# motor_shield__SD_v2_0.net
KiCad netlist of a schematic drawn in EAGLE
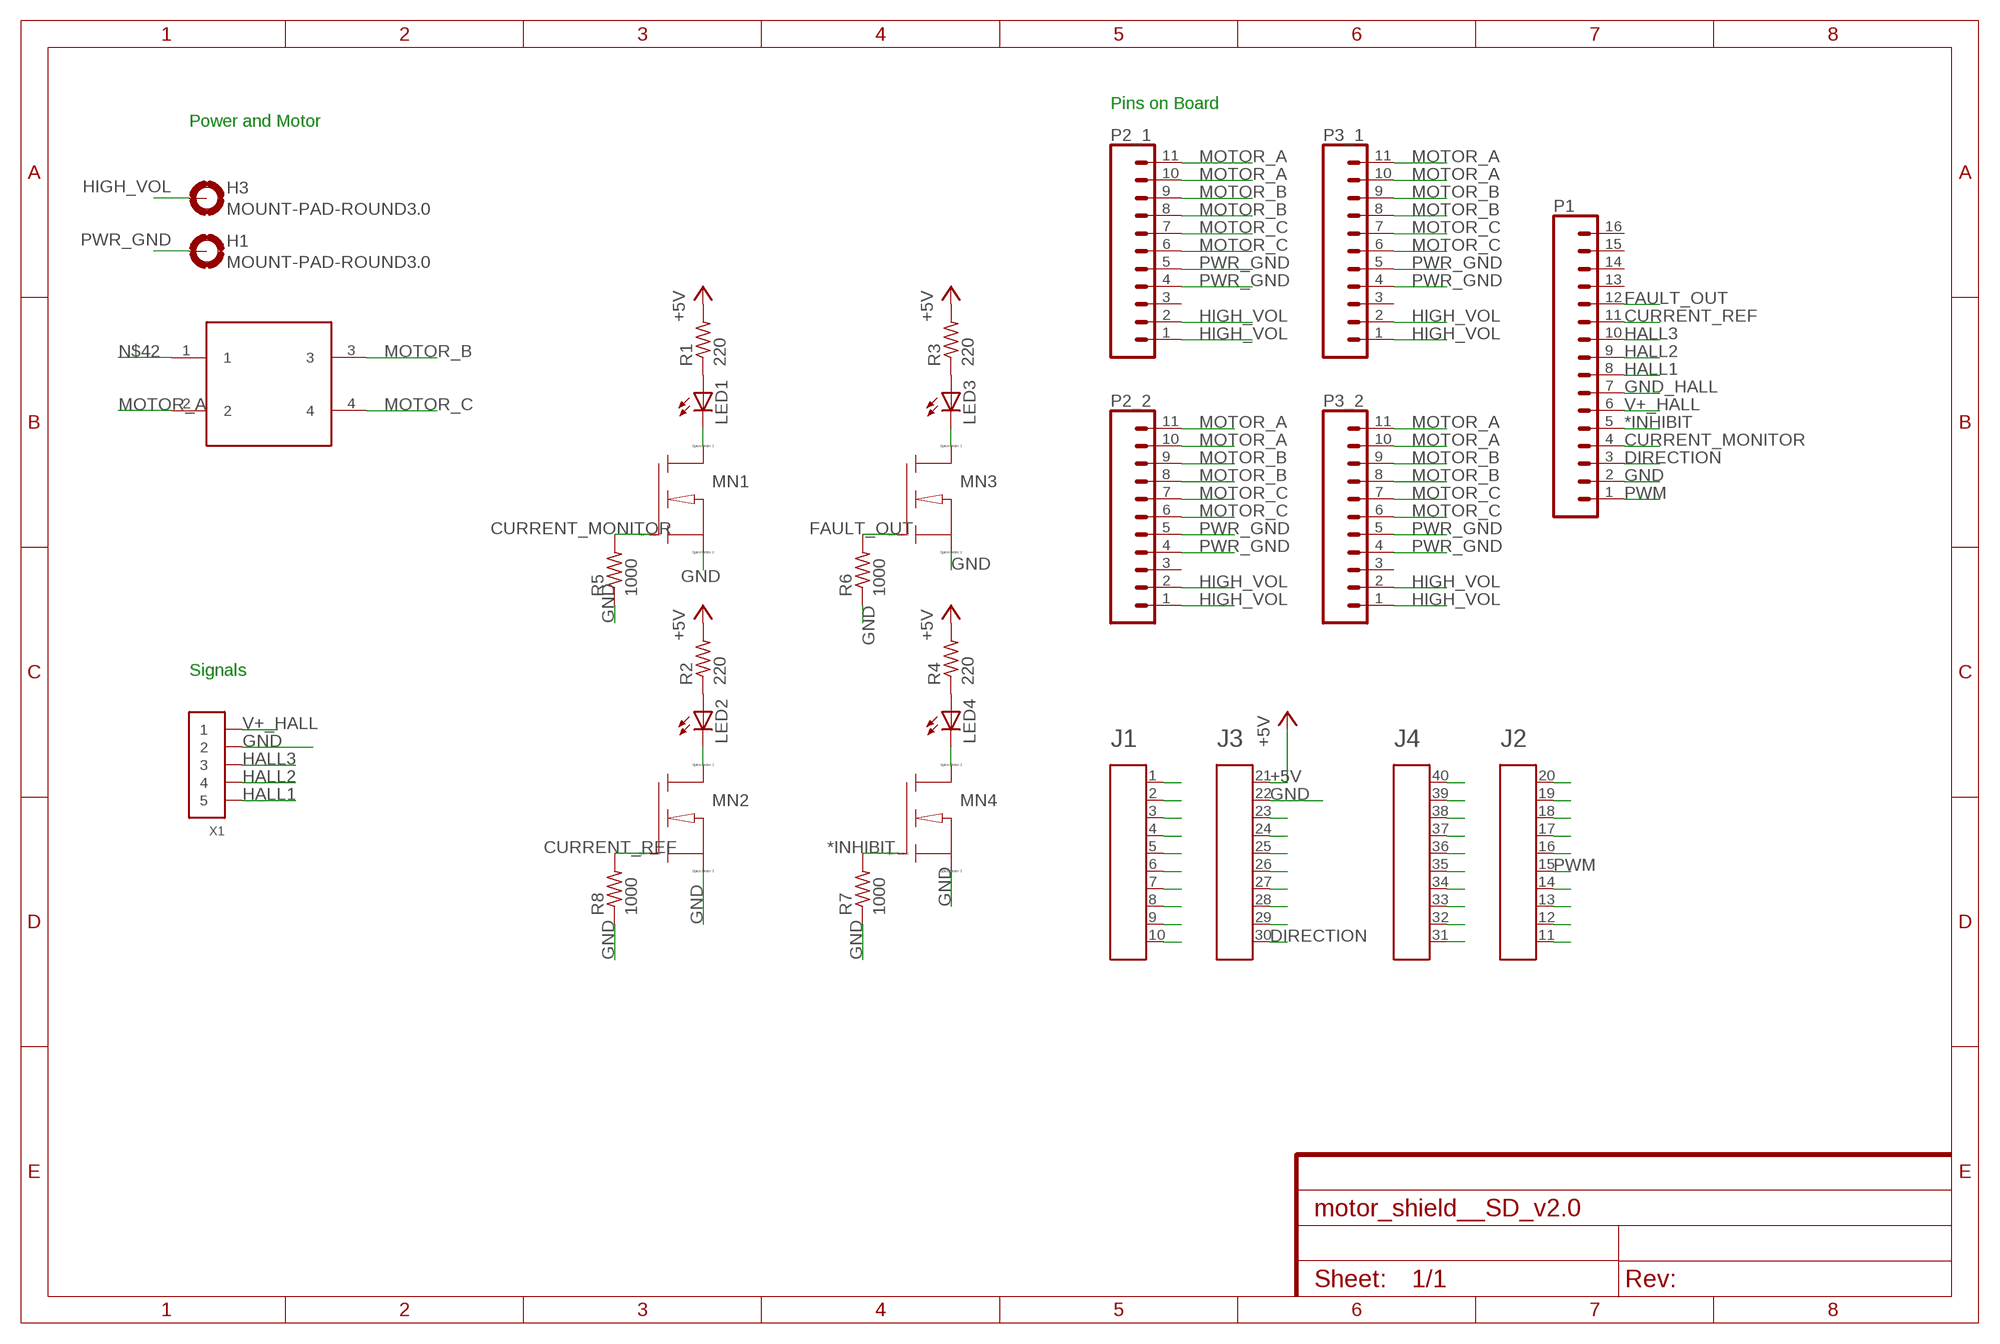
[diagram p0: schematic, sheet 1]

(export (version "E")
  (design (tool "Eeschema 10.0.6"))
  (components
    (comp (ref "A1")
      (value "HEADER4X10-BOOSTERPACK")
      (footprint "eagle-import:4X10-BOOSTERPACK")
      (libsource (lib "eagle-import") (part "HEADER4X10-BOOSTERPACK"))
    )
    (comp (ref "H1")
      (value "MOUNT-PAD-ROUND3.0")
      (footprint "eagle-import:3,0-PAD")
      (libsource (lib "eagle-import") (part "MOUNT-PAD-ROUND3.0"))
    )
    (comp (ref "H3")
      (value "MOUNT-PAD-ROUND3.0")
      (footprint "eagle-import:3,0-PAD")
      (libsource (lib "eagle-import") (part "MOUNT-PAD-ROUND3.0"))
    )
    (comp (ref "LED1")
      (value "LEDCHIPLED_0805")
      (footprint "eagle-import:CHIPLED_0805")
      (libsource (lib "eagle-import") (part "LEDCHIPLED_0805"))
    )
    (comp (ref "LED2")
      (value "LEDCHIPLED_0805")
      (footprint "eagle-import:CHIPLED_0805")
      (libsource (lib "eagle-import") (part "LEDCHIPLED_0805"))
    )
    (comp (ref "LED3")
      (value "LEDCHIPLED_0805")
      (footprint "eagle-import:CHIPLED_0805")
      (libsource (lib "eagle-import") (part "LEDCHIPLED_0805"))
    )
    (comp (ref "LED4")
      (value "LEDCHIPLED_0805")
      (footprint "eagle-import:CHIPLED_0805")
      (libsource (lib "eagle-import") (part "LEDCHIPLED_0805"))
    )
    (comp (ref "MN1")
      (value "NMOS")
      (footprint "eagle-import:SOT23")
      (libsource (lib "eagle-import") (part "NMOS"))
    )
    (comp (ref "MN2")
      (value "NMOS")
      (footprint "eagle-import:SOT23")
      (libsource (lib "eagle-import") (part "NMOS"))
    )
    (comp (ref "MN3")
      (value "NMOS")
      (footprint "eagle-import:SOT23")
      (libsource (lib "eagle-import") (part "NMOS"))
    )
    (comp (ref "MN4")
      (value "NMOS")
      (footprint "eagle-import:SOT23")
      (libsource (lib "eagle-import") (part "NMOS"))
    )
    (comp (ref "P1")
      (value "CONN_16LOCK")
      (footprint "eagle-import:1X16_LOCK")
      (libsource (lib "eagle-import") (part "CONN_16LOCK"))
    )
    (comp (ref "P2_1")
      (value "CONN_11")
      (footprint "eagle-import:1X11")
      (libsource (lib "eagle-import") (part "CONN_11"))
    )
    (comp (ref "P2_2")
      (value "CONN_11")
      (footprint "eagle-import:1X11")
      (libsource (lib "eagle-import") (part "CONN_11"))
    )
    (comp (ref "P3_1")
      (value "CONN_11")
      (footprint "eagle-import:1X11")
      (libsource (lib "eagle-import") (part "CONN_11"))
    )
    (comp (ref "P3_2")
      (value "CONN_11")
      (footprint "eagle-import:1X11")
      (libsource (lib "eagle-import") (part "CONN_11"))
    )
    (comp (ref "R1")
      (value "220")
      (footprint "eagle-import:R0603")
      (libsource (lib "eagle-import") (part "R-US_R0603"))
    )
    (comp (ref "R2")
      (value "220")
      (footprint "eagle-import:R0603")
      (libsource (lib "eagle-import") (part "R-US_R0603"))
    )
    (comp (ref "R3")
      (value "220")
      (footprint "eagle-import:R0603")
      (libsource (lib "eagle-import") (part "R-US_R0603"))
    )
    (comp (ref "R4")
      (value "220")
      (footprint "eagle-import:R0603")
      (libsource (lib "eagle-import") (part "R-US_R0603"))
    )
    (comp (ref "R5")
      (value "1000")
      (footprint "eagle-import:R0603")
      (libsource (lib "eagle-import") (part "R-US_R0603"))
    )
    (comp (ref "R6")
      (value "1000")
      (footprint "eagle-import:R0603")
      (libsource (lib "eagle-import") (part "R-US_R0603"))
    )
    (comp (ref "R7")
      (value "1000")
      (footprint "eagle-import:R0603")
      (libsource (lib "eagle-import") (part "R-US_R0603"))
    )
    (comp (ref "R8")
      (value "1000")
      (footprint "eagle-import:R0603")
      (libsource (lib "eagle-import") (part "R-US_R0603"))
    )
    (comp (ref "U$2")
      (value "MOLEX4CON")
      (footprint "eagle-import:MOLEX4CON")
      (libsource (lib "eagle-import") (part "MOLEX4CON"))
    )
    (comp (ref "X1")
      (value "CONN_5-1-53261")
      (footprint "eagle-import:PB-53261-05")
      (libsource (lib "eagle-import") (part "CONN_5-1-53261"))
    )
  )
  (nets
    (net (code "1") (name "+5V") (class "Default")
      (node (ref "A1") (pin "21") (pinfunction "P$21_21") (pintype "bidirectional"))
      (node (ref "R1") (pin "2") (pinfunction "2_2") (pintype "passive"))
      (node (ref "R2") (pin "2") (pinfunction "2_2") (pintype "passive"))
      (node (ref "R3") (pin "2") (pinfunction "2_2") (pintype "passive"))
      (node (ref "R4") (pin "2") (pinfunction "2_2") (pintype "passive"))
    )
    (net (code "2") (name "/*INHIBIT") (class "Default")
      (node (ref "MN4") (pin "1") (pinfunction "G_1") (pintype "passive"))
      (node (ref "P1") (pin "5") (pinfunction "5_5") (pintype "passive"))
      (node (ref "R7") (pin "2") (pinfunction "2_2") (pintype "passive"))
    )
    (net (code "3") (name "/CURRENT_MONITOR") (class "Default")
      (node (ref "MN1") (pin "1") (pinfunction "G_1") (pintype "passive"))
      (node (ref "P1") (pin "4") (pinfunction "4_4") (pintype "passive"))
      (node (ref "R5") (pin "2") (pinfunction "2_2") (pintype "passive"))
    )
    (net (code "4") (name "/CURRENT_REF") (class "Default")
      (node (ref "MN2") (pin "1") (pinfunction "G_1") (pintype "passive"))
      (node (ref "P1") (pin "11") (pinfunction "11_11") (pintype "passive"))
      (node (ref "R8") (pin "2") (pinfunction "2_2") (pintype "passive"))
    )
    (net (code "5") (name "/DIRECTION") (class "Default")
      (node (ref "A1") (pin "30") (pinfunction "P$30_30") (pintype "bidirectional"))
      (node (ref "P1") (pin "3") (pinfunction "3_3") (pintype "passive"))
    )
    (net (code "6") (name "/FAULT_OUT") (class "Default")
      (node (ref "MN3") (pin "1") (pinfunction "G_1") (pintype "passive"))
      (node (ref "P1") (pin "12") (pinfunction "12_12") (pintype "passive"))
      (node (ref "R6") (pin "2") (pinfunction "2_2") (pintype "passive"))
    )
    (net (code "7") (name "/GND") (class "Default")
      (node (ref "A1") (pin "22") (pinfunction "P$22_22") (pintype "bidirectional"))
      (node (ref "MN1") (pin "2") (pinfunction "S_2") (pintype "passive"))
      (node (ref "MN2") (pin "2") (pinfunction "S_2") (pintype "passive"))
      (node (ref "MN3") (pin "2") (pinfunction "S_2") (pintype "passive"))
      (node (ref "MN4") (pin "2") (pinfunction "S_2") (pintype "passive"))
      (node (ref "P1") (pin "2") (pinfunction "2_2") (pintype "passive"))
      (node (ref "R5") (pin "1") (pinfunction "1_1") (pintype "passive"))
      (node (ref "R6") (pin "1") (pinfunction "1_1") (pintype "passive"))
      (node (ref "R7") (pin "1") (pinfunction "1_1") (pintype "passive"))
      (node (ref "R8") (pin "1") (pinfunction "1_1") (pintype "passive"))
      (node (ref "X1") (pin "2") (pinfunction "2_2") (pintype "bidirectional"))
    )
    (net (code "8") (name "/GND_HALL") (class "Default")
      (node (ref "P1") (pin "7") (pinfunction "7_7") (pintype "passive"))
    )
    (net (code "9") (name "/HALL1") (class "Default")
      (node (ref "P1") (pin "8") (pinfunction "8_8") (pintype "passive"))
      (node (ref "X1") (pin "5") (pinfunction "5_5") (pintype "bidirectional"))
    )
    (net (code "10") (name "/HALL2") (class "Default")
      (node (ref "P1") (pin "9") (pinfunction "9_9") (pintype "passive"))
      (node (ref "X1") (pin "4") (pinfunction "4_4") (pintype "bidirectional"))
    )
    (net (code "11") (name "/HALL3") (class "Default")
      (node (ref "P1") (pin "10") (pinfunction "10_10") (pintype "passive"))
      (node (ref "X1") (pin "3") (pinfunction "3_3") (pintype "bidirectional"))
    )
    (net (code "12") (name "/HIGH_VOL") (class "Default")
      (node (ref "H3") (pin "B3,0") (pinfunction "MOUNT_B3,0") (pintype "passive"))
      (node (ref "P2_1") (pin "1") (pinfunction "1_1") (pintype "passive"))
      (node (ref "P2_1") (pin "2") (pinfunction "2_2") (pintype "passive"))
      (node (ref "P2_2") (pin "1") (pinfunction "1_1") (pintype "passive"))
      (node (ref "P2_2") (pin "2") (pinfunction "2_2") (pintype "passive"))
      (node (ref "P3_1") (pin "1") (pinfunction "1_1") (pintype "passive"))
      (node (ref "P3_1") (pin "2") (pinfunction "2_2") (pintype "passive"))
      (node (ref "P3_2") (pin "1") (pinfunction "1_1") (pintype "passive"))
      (node (ref "P3_2") (pin "2") (pinfunction "2_2") (pintype "passive"))
    )
    (net (code "13") (name "/MOTOR_A") (class "Default")
      (node (ref "P2_1") (pin "10") (pinfunction "10_10") (pintype "passive"))
      (node (ref "P2_1") (pin "11") (pinfunction "11_11") (pintype "passive"))
      (node (ref "P2_2") (pin "10") (pinfunction "10_10") (pintype "passive"))
      (node (ref "P2_2") (pin "11") (pinfunction "11_11") (pintype "passive"))
      (node (ref "P3_1") (pin "10") (pinfunction "10_10") (pintype "passive"))
      (node (ref "P3_1") (pin "11") (pinfunction "11_11") (pintype "passive"))
      (node (ref "P3_2") (pin "10") (pinfunction "10_10") (pintype "passive"))
      (node (ref "P3_2") (pin "11") (pinfunction "11_11") (pintype "passive"))
      (node (ref "U$2") (pin "2") (pinfunction "2_2") (pintype "bidirectional"))
    )
    (net (code "14") (name "/MOTOR_B") (class "Default")
      (node (ref "P2_1") (pin "8") (pinfunction "8_8") (pintype "passive"))
      (node (ref "P2_1") (pin "9") (pinfunction "9_9") (pintype "passive"))
      (node (ref "P2_2") (pin "8") (pinfunction "8_8") (pintype "passive"))
      (node (ref "P2_2") (pin "9") (pinfunction "9_9") (pintype "passive"))
      (node (ref "P3_1") (pin "8") (pinfunction "8_8") (pintype "passive"))
      (node (ref "P3_1") (pin "9") (pinfunction "9_9") (pintype "passive"))
      (node (ref "P3_2") (pin "8") (pinfunction "8_8") (pintype "passive"))
      (node (ref "P3_2") (pin "9") (pinfunction "9_9") (pintype "passive"))
      (node (ref "U$2") (pin "3") (pinfunction "3_3") (pintype "bidirectional"))
    )
    (net (code "15") (name "/MOTOR_C") (class "Default")
      (node (ref "P2_1") (pin "6") (pinfunction "6_6") (pintype "passive"))
      (node (ref "P2_1") (pin "7") (pinfunction "7_7") (pintype "passive"))
      (node (ref "P2_2") (pin "6") (pinfunction "6_6") (pintype "passive"))
      (node (ref "P2_2") (pin "7") (pinfunction "7_7") (pintype "passive"))
      (node (ref "P3_1") (pin "6") (pinfunction "6_6") (pintype "passive"))
      (node (ref "P3_1") (pin "7") (pinfunction "7_7") (pintype "passive"))
      (node (ref "P3_2") (pin "6") (pinfunction "6_6") (pintype "passive"))
      (node (ref "P3_2") (pin "7") (pinfunction "7_7") (pintype "passive"))
      (node (ref "U$2") (pin "4") (pinfunction "4_4") (pintype "bidirectional"))
    )
    (net (code "16") (name "/N$42") (class "Default")
      (node (ref "U$2") (pin "1") (pinfunction "1_1") (pintype "bidirectional"))
    )
    (net (code "17") (name "/PWM") (class "Default")
      (node (ref "A1") (pin "15") (pinfunction "P$15_15") (pintype "bidirectional"))
      (node (ref "P1") (pin "1") (pinfunction "1_1") (pintype "passive"))
    )
    (net (code "18") (name "/PWR_GND") (class "Default")
      (node (ref "H1") (pin "B3,0") (pinfunction "MOUNT_B3,0") (pintype "passive"))
      (node (ref "P2_1") (pin "4") (pinfunction "4_4") (pintype "passive"))
      (node (ref "P2_1") (pin "5") (pinfunction "5_5") (pintype "passive"))
      (node (ref "P2_2") (pin "4") (pinfunction "4_4") (pintype "passive"))
      (node (ref "P2_2") (pin "5") (pinfunction "5_5") (pintype "passive"))
      (node (ref "P3_1") (pin "4") (pinfunction "4_4") (pintype "passive"))
      (node (ref "P3_1") (pin "5") (pinfunction "5_5") (pintype "passive"))
      (node (ref "P3_2") (pin "4") (pinfunction "4_4") (pintype "passive"))
      (node (ref "P3_2") (pin "5") (pinfunction "5_5") (pintype "passive"))
    )
    (net (code "19") (name "/V+_HALL") (class "Default")
      (node (ref "P1") (pin "6") (pinfunction "6_6") (pintype "passive"))
      (node (ref "X1") (pin "1") (pinfunction "1_1") (pintype "bidirectional"))
    )
    (net (code "20") (name "Net-(LED1-PadA)") (class "Default")
      (node (ref "LED1") (pin "A") (pinfunction "A_A") (pintype "passive"))
      (node (ref "R1") (pin "1") (pinfunction "1_1") (pintype "passive"))
    )
    (net (code "21") (name "Net-(LED2-PadA)") (class "Default")
      (node (ref "LED2") (pin "A") (pinfunction "A_A") (pintype "passive"))
      (node (ref "R2") (pin "1") (pinfunction "1_1") (pintype "passive"))
    )
    (net (code "22") (name "Net-(LED3-PadA)") (class "Default")
      (node (ref "LED3") (pin "A") (pinfunction "A_A") (pintype "passive"))
      (node (ref "R3") (pin "1") (pinfunction "1_1") (pintype "passive"))
    )
    (net (code "23") (name "Net-(LED4-PadA)") (class "Default")
      (node (ref "LED4") (pin "A") (pinfunction "A_A") (pintype "passive"))
      (node (ref "R4") (pin "1") (pinfunction "1_1") (pintype "passive"))
    )
    (net (code "24") (name "Net-(MN1-D)") (class "Default")
      (node (ref "LED1") (pin "C") (pinfunction "C_C") (pintype "passive"))
      (node (ref "MN1") (pin "3") (pinfunction "D_3") (pintype "passive"))
    )
    (net (code "25") (name "Net-(MN2-D)") (class "Default")
      (node (ref "LED2") (pin "C") (pinfunction "C_C") (pintype "passive"))
      (node (ref "MN2") (pin "3") (pinfunction "D_3") (pintype "passive"))
    )
    (net (code "26") (name "Net-(MN3-D)") (class "Default")
      (node (ref "LED3") (pin "C") (pinfunction "C_C") (pintype "passive"))
      (node (ref "MN3") (pin "3") (pinfunction "D_3") (pintype "passive"))
    )
    (net (code "27") (name "Net-(MN4-D)") (class "Default")
      (node (ref "LED4") (pin "C") (pinfunction "C_C") (pintype "passive"))
      (node (ref "MN4") (pin "3") (pinfunction "D_3") (pintype "passive"))
    )
    (net (code "28") (name "unconnected-(A1-P$1-Pad1)") (class "Default")
      (node (ref "A1") (pin "1") (pinfunction "P$1_1") (pintype "bidirectional"))
    )
    (net (code "29") (name "unconnected-(A1-P$2-Pad2)") (class "Default")
      (node (ref "A1") (pin "2") (pinfunction "P$2_2") (pintype "bidirectional"))
    )
    (net (code "30") (name "unconnected-(A1-P$3-Pad3)") (class "Default")
      (node (ref "A1") (pin "3") (pinfunction "P$3_3") (pintype "bidirectional"))
    )
    (net (code "31") (name "unconnected-(A1-P$4-Pad4)") (class "Default")
      (node (ref "A1") (pin "4") (pinfunction "P$4_4") (pintype "bidirectional"))
    )
    (net (code "32") (name "unconnected-(A1-P$5-Pad5)") (class "Default")
      (node (ref "A1") (pin "5") (pinfunction "P$5_5") (pintype "bidirectional"))
    )
    (net (code "33") (name "unconnected-(A1-P$6-Pad6)") (class "Default")
      (node (ref "A1") (pin "6") (pinfunction "P$6_6") (pintype "bidirectional"))
    )
    (net (code "34") (name "unconnected-(A1-P$7-Pad7)") (class "Default")
      (node (ref "A1") (pin "7") (pinfunction "P$7_7") (pintype "bidirectional"))
    )
    (net (code "35") (name "unconnected-(A1-P$8-Pad8)") (class "Default")
      (node (ref "A1") (pin "8") (pinfunction "P$8_8") (pintype "bidirectional"))
    )
    (net (code "36") (name "unconnected-(A1-P$9-Pad9)") (class "Default")
      (node (ref "A1") (pin "9") (pinfunction "P$9_9") (pintype "bidirectional"))
    )
    (net (code "37") (name "unconnected-(A1-P$10-Pad10)") (class "Default")
      (node (ref "A1") (pin "10") (pinfunction "P$10_10") (pintype "bidirectional"))
    )
    (net (code "38") (name "unconnected-(A1-P$11-Pad11)") (class "Default")
      (node (ref "A1") (pin "11") (pinfunction "P$11_11") (pintype "bidirectional"))
    )
    (net (code "39") (name "unconnected-(A1-P$12-Pad12)") (class "Default")
      (node (ref "A1") (pin "12") (pinfunction "P$12_12") (pintype "bidirectional"))
    )
    (net (code "40") (name "unconnected-(A1-P$13-Pad13)") (class "Default")
      (node (ref "A1") (pin "13") (pinfunction "P$13_13") (pintype "bidirectional"))
    )
    (net (code "41") (name "unconnected-(A1-P$14-Pad14)") (class "Default")
      (node (ref "A1") (pin "14") (pinfunction "P$14_14") (pintype "bidirectional"))
    )
    (net (code "42") (name "unconnected-(A1-P$16-Pad16)") (class "Default")
      (node (ref "A1") (pin "16") (pinfunction "P$16_16") (pintype "bidirectional"))
    )
    (net (code "43") (name "unconnected-(A1-P$17-Pad17)") (class "Default")
      (node (ref "A1") (pin "17") (pinfunction "P$17_17") (pintype "bidirectional"))
    )
    (net (code "44") (name "unconnected-(A1-P$18-Pad18)") (class "Default")
      (node (ref "A1") (pin "18") (pinfunction "P$18_18") (pintype "bidirectional"))
    )
    (net (code "45") (name "unconnected-(A1-P$19-Pad19)") (class "Default")
      (node (ref "A1") (pin "19") (pinfunction "P$19_19") (pintype "bidirectional"))
    )
    (net (code "46") (name "unconnected-(A1-P$20-Pad20)") (class "Default")
      (node (ref "A1") (pin "20") (pinfunction "P$20_20") (pintype "bidirectional"))
    )
    (net (code "47") (name "unconnected-(A1-P$23-Pad23)") (class "Default")
      (node (ref "A1") (pin "23") (pinfunction "P$23_23") (pintype "bidirectional"))
    )
    (net (code "48") (name "unconnected-(A1-P$24-Pad24)") (class "Default")
      (node (ref "A1") (pin "24") (pinfunction "P$24_24") (pintype "bidirectional"))
    )
    (net (code "49") (name "unconnected-(A1-P$25-Pad25)") (class "Default")
      (node (ref "A1") (pin "25") (pinfunction "P$25_25") (pintype "bidirectional"))
    )
    (net (code "50") (name "unconnected-(A1-P$26-Pad26)") (class "Default")
      (node (ref "A1") (pin "26") (pinfunction "P$26_26") (pintype "bidirectional"))
    )
    (net (code "51") (name "unconnected-(A1-P$27-Pad27)") (class "Default")
      (node (ref "A1") (pin "27") (pinfunction "P$27_27") (pintype "bidirectional"))
    )
    (net (code "52") (name "unconnected-(A1-P$28-Pad28)") (class "Default")
      (node (ref "A1") (pin "28") (pinfunction "P$28_28") (pintype "bidirectional"))
    )
    (net (code "53") (name "unconnected-(A1-P$29-Pad29)") (class "Default")
      (node (ref "A1") (pin "29") (pinfunction "P$29_29") (pintype "bidirectional"))
    )
    (net (code "54") (name "unconnected-(A1-P$31-Pad31)") (class "Default")
      (node (ref "A1") (pin "31") (pinfunction "P$31_31") (pintype "bidirectional"))
    )
    (net (code "55") (name "unconnected-(A1-P$32-Pad32)") (class "Default")
      (node (ref "A1") (pin "32") (pinfunction "P$32_32") (pintype "bidirectional"))
    )
    (net (code "56") (name "unconnected-(A1-P$33-Pad33)") (class "Default")
      (node (ref "A1") (pin "33") (pinfunction "P$33_33") (pintype "bidirectional"))
    )
    (net (code "57") (name "unconnected-(A1-P$34-Pad34)") (class "Default")
      (node (ref "A1") (pin "34") (pinfunction "P$34_34") (pintype "bidirectional"))
    )
    (net (code "58") (name "unconnected-(A1-P$35-Pad35)") (class "Default")
      (node (ref "A1") (pin "35") (pinfunction "P$35_35") (pintype "bidirectional"))
    )
    (net (code "59") (name "unconnected-(A1-P$36-Pad36)") (class "Default")
      (node (ref "A1") (pin "36") (pinfunction "P$36_36") (pintype "bidirectional"))
    )
    (net (code "60") (name "unconnected-(A1-P$37-Pad37)") (class "Default")
      (node (ref "A1") (pin "37") (pinfunction "P$37_37") (pintype "bidirectional"))
    )
    (net (code "61") (name "unconnected-(A1-P$38-Pad38)") (class "Default")
      (node (ref "A1") (pin "38") (pinfunction "P$38_38") (pintype "bidirectional"))
    )
    (net (code "62") (name "unconnected-(A1-P$39-Pad39)") (class "Default")
      (node (ref "A1") (pin "39") (pinfunction "P$39_39") (pintype "bidirectional"))
    )
    (net (code "63") (name "unconnected-(A1-P$40-Pad40)") (class "Default")
      (node (ref "A1") (pin "40") (pinfunction "P$40_40") (pintype "bidirectional"))
    )
    (net (code "64") (name "unconnected-(P1-Pad13)") (class "Default")
      (node (ref "P1") (pin "13") (pinfunction "13_13") (pintype "passive"))
    )
    (net (code "65") (name "unconnected-(P1-Pad14)") (class "Default")
      (node (ref "P1") (pin "14") (pinfunction "14_14") (pintype "passive"))
    )
    (net (code "66") (name "unconnected-(P1-Pad15)") (class "Default")
      (node (ref "P1") (pin "15") (pinfunction "15_15") (pintype "passive"))
    )
    (net (code "67") (name "unconnected-(P1-Pad16)") (class "Default")
      (node (ref "P1") (pin "16") (pinfunction "16_16") (pintype "passive"))
    )
    (net (code "68") (name "unconnected-(P2_1-Pad3)") (class "Default")
      (node (ref "P2_1") (pin "3") (pinfunction "3_3") (pintype "passive"))
    )
    (net (code "69") (name "unconnected-(P2_2-Pad3)") (class "Default")
      (node (ref "P2_2") (pin "3") (pinfunction "3_3") (pintype "passive"))
    )
    (net (code "70") (name "unconnected-(P3_1-Pad3)") (class "Default")
      (node (ref "P3_1") (pin "3") (pinfunction "3_3") (pintype "passive"))
    )
    (net (code "71") (name "unconnected-(P3_2-Pad3)") (class "Default")
      (node (ref "P3_2") (pin "3") (pinfunction "3_3") (pintype "passive"))
    )
  )
)
